# WiFi_Card_Led_Monitor.net
KiCad netlist of a schematic drawn in Altium Designer
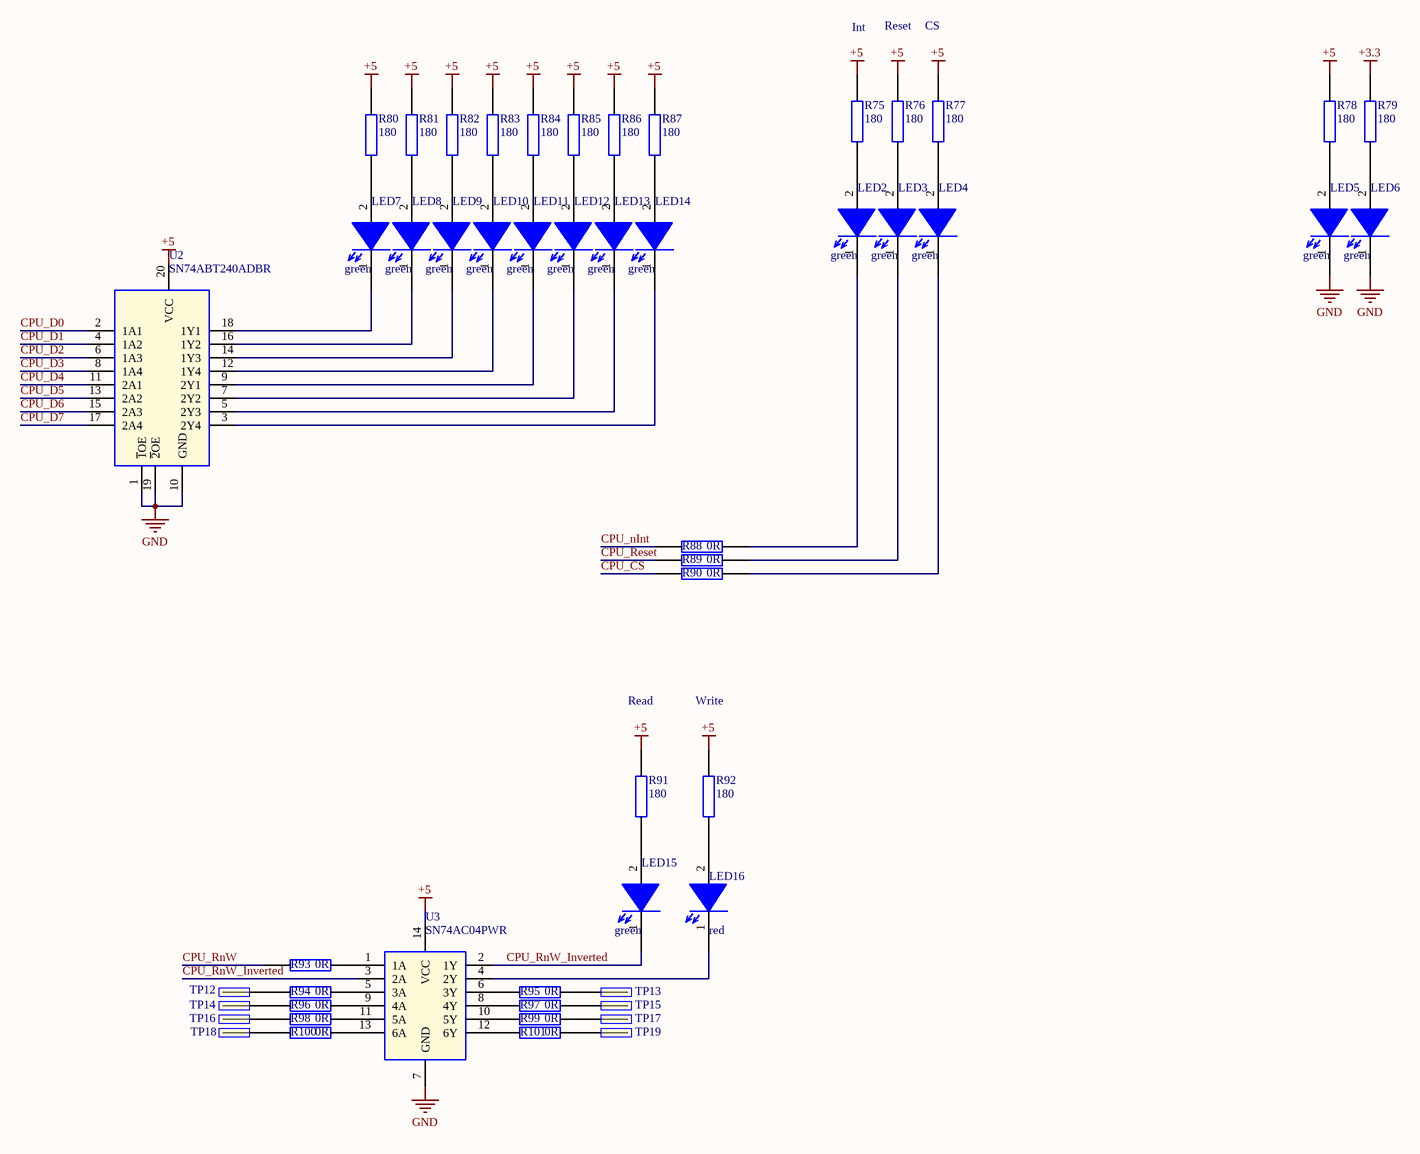
[diagram p0: WiFi_Card_Led_Monitor.SchDoc]

(export (version "E")
  (design (tool "Eeschema 10.0.6"))
  (components
    (comp (ref "LED2")
      (value "green")
      (footprint "0603_Diode")
      (description "Wurth Elektronik 0603 green")
      (fields
        (field (name "MANUFACTURER") "Wurth Electronics")
        (field (name "MANUFACTURER PART NUMBER") "150060GS75000")
      )
      (libsource (lib "Misc") (part "150060GS75000"))
    )
    (comp (ref "LED3")
      (value "green")
      (footprint "0603_Diode")
      (description "Wurth Elektronik 0603 green")
      (fields
        (field (name "MANUFACTURER") "Wurth Electronics")
        (field (name "MANUFACTURER PART NUMBER") "150060GS75000")
      )
      (libsource (lib "Misc") (part "150060GS75000"))
    )
    (comp (ref "LED4")
      (value "green")
      (footprint "0603_Diode")
      (description "Wurth Elektronik 0603 green")
      (fields
        (field (name "MANUFACTURER") "Wurth Electronics")
        (field (name "MANUFACTURER PART NUMBER") "150060GS75000")
      )
      (libsource (lib "Misc") (part "150060GS75000"))
    )
    (comp (ref "LED5")
      (value "green")
      (footprint "0603_Diode")
      (description "Wurth Elektronik 0603 green")
      (fields
        (field (name "MANUFACTURER") "Wurth Electronics")
        (field (name "MANUFACTURER PART NUMBER") "150060GS75000")
      )
      (libsource (lib "Misc") (part "150060GS75000"))
    )
    (comp (ref "LED6")
      (value "green")
      (footprint "0603_Diode")
      (description "Wurth Elektronik 0603 green")
      (fields
        (field (name "MANUFACTURER") "Wurth Electronics")
        (field (name "MANUFACTURER PART NUMBER") "150060GS75000")
      )
      (libsource (lib "Misc") (part "150060GS75000"))
    )
    (comp (ref "LED7")
      (value "green")
      (footprint "0603_Diode")
      (description "Wurth Elektronik 0603 green")
      (fields
        (field (name "MANUFACTURER") "Wurth Electronics")
        (field (name "MANUFACTURER PART NUMBER") "150060GS75000")
      )
      (libsource (lib "Misc") (part "150060GS75000"))
    )
    (comp (ref "LED8")
      (value "green")
      (footprint "0603_Diode")
      (description "Wurth Elektronik 0603 green")
      (fields
        (field (name "MANUFACTURER") "Wurth Electronics")
        (field (name "MANUFACTURER PART NUMBER") "150060GS75000")
      )
      (libsource (lib "Misc") (part "150060GS75000"))
    )
    (comp (ref "LED9")
      (value "green")
      (footprint "0603_Diode")
      (description "Wurth Elektronik 0603 green")
      (fields
        (field (name "MANUFACTURER") "Wurth Electronics")
        (field (name "MANUFACTURER PART NUMBER") "150060GS75000")
      )
      (libsource (lib "Misc") (part "150060GS75000"))
    )
    (comp (ref "LED10")
      (value "green")
      (footprint "0603_Diode")
      (description "Wurth Elektronik 0603 green")
      (fields
        (field (name "MANUFACTURER") "Wurth Electronics")
        (field (name "MANUFACTURER PART NUMBER") "150060GS75000")
      )
      (libsource (lib "Misc") (part "150060GS75000"))
    )
    (comp (ref "LED11")
      (value "green")
      (footprint "0603_Diode")
      (description "Wurth Elektronik 0603 green")
      (fields
        (field (name "MANUFACTURER") "Wurth Electronics")
        (field (name "MANUFACTURER PART NUMBER") "150060GS75000")
      )
      (libsource (lib "Misc") (part "150060GS75000"))
    )
    (comp (ref "LED12")
      (value "green")
      (footprint "0603_Diode")
      (description "Wurth Elektronik 0603 green")
      (fields
        (field (name "MANUFACTURER") "Wurth Electronics")
        (field (name "MANUFACTURER PART NUMBER") "150060GS75000")
      )
      (libsource (lib "Misc") (part "150060GS75000"))
    )
    (comp (ref "LED13")
      (value "green")
      (footprint "0603_Diode")
      (description "Wurth Elektronik 0603 green")
      (fields
        (field (name "MANUFACTURER") "Wurth Electronics")
        (field (name "MANUFACTURER PART NUMBER") "150060GS75000")
      )
      (libsource (lib "Misc") (part "150060GS75000"))
    )
    (comp (ref "LED14")
      (value "green")
      (footprint "0603_Diode")
      (description "Wurth Elektronik 0603 green")
      (fields
        (field (name "MANUFACTURER") "Wurth Electronics")
        (field (name "MANUFACTURER PART NUMBER") "150060GS75000")
      )
      (libsource (lib "Misc") (part "150060GS75000"))
    )
    (comp (ref "LED15")
      (value "green")
      (footprint "0603_Diode")
      (description "Wurth Elektronik 0603 green")
      (fields
        (field (name "MANUFACTURER") "Wurth Electronics")
        (field (name "MANUFACTURER PART NUMBER") "150060GS75000")
      )
      (libsource (lib "Misc") (part "150060GS75000"))
    )
    (comp (ref "LED16")
      (value "red")
      (footprint "0603_Diode")
      (description "Wurth Elektronik 0603 red")
      (fields
        (field (name "MANUFACTURER") "Wurth Electronics")
        (field (name "MANUFACTURER PART NUMBER") "150060GS75000")
      )
      (libsource (lib "Misc") (part "150060RS75000"))
    )
    (comp (ref "R75")
      (value "180")
      (footprint "0603")
      (description "YAGEO 0603 180 ohm")
      (fields
        (field (name "MOUSER PART NUMBER") "603-RC0603JR-070RL")
        (field (name "MANUFACTURER_PART_NUMBER") "RC0603JR-070RL")
      )
      (libsource (lib "Resistors") (part "RC0603FR-13180RL"))
    )
    (comp (ref "R76")
      (value "180")
      (footprint "0603")
      (description "YAGEO 0603 180 ohm")
      (fields
        (field (name "MOUSER PART NUMBER") "603-RC0603JR-070RL")
        (field (name "MANUFACTURER_PART_NUMBER") "RC0603JR-070RL")
      )
      (libsource (lib "Resistors") (part "RC0603FR-13180RL"))
    )
    (comp (ref "R77")
      (value "180")
      (footprint "0603")
      (description "YAGEO 0603 180 ohm")
      (fields
        (field (name "MOUSER PART NUMBER") "603-RC0603JR-070RL")
        (field (name "MANUFACTURER_PART_NUMBER") "RC0603JR-070RL")
      )
      (libsource (lib "Resistors") (part "RC0603FR-13180RL"))
    )
    (comp (ref "R78")
      (value "180")
      (footprint "0603")
      (description "YAGEO 0603 180 ohm")
      (fields
        (field (name "MOUSER PART NUMBER") "603-RC0603JR-070RL")
        (field (name "MANUFACTURER_PART_NUMBER") "RC0603JR-070RL")
      )
      (libsource (lib "Resistors") (part "RC0603FR-13180RL"))
    )
    (comp (ref "R79")
      (value "180")
      (footprint "0603")
      (description "YAGEO 0603 180 ohm")
      (fields
        (field (name "MOUSER PART NUMBER") "603-RC0603JR-070RL")
        (field (name "MANUFACTURER_PART_NUMBER") "RC0603JR-070RL")
      )
      (libsource (lib "Resistors") (part "RC0603FR-13180RL"))
    )
    (comp (ref "R80")
      (value "180")
      (footprint "0603")
      (description "YAGEO 0603 180 ohm")
      (fields
        (field (name "MOUSER PART NUMBER") "603-RC0603JR-070RL")
        (field (name "MANUFACTURER_PART_NUMBER") "RC0603JR-070RL")
      )
      (libsource (lib "Resistors") (part "RC0603FR-13180RL"))
    )
    (comp (ref "R81")
      (value "180")
      (footprint "0603")
      (description "YAGEO 0603 180 ohm")
      (fields
        (field (name "MOUSER PART NUMBER") "603-RC0603JR-070RL")
        (field (name "MANUFACTURER_PART_NUMBER") "RC0603JR-070RL")
      )
      (libsource (lib "Resistors") (part "RC0603FR-13180RL"))
    )
    (comp (ref "R82")
      (value "180")
      (footprint "0603")
      (description "YAGEO 0603 180 ohm")
      (fields
        (field (name "MOUSER PART NUMBER") "603-RC0603JR-070RL")
        (field (name "MANUFACTURER_PART_NUMBER") "RC0603JR-070RL")
      )
      (libsource (lib "Resistors") (part "RC0603FR-13180RL"))
    )
    (comp (ref "R83")
      (value "180")
      (footprint "0603")
      (description "YAGEO 0603 180 ohm")
      (fields
        (field (name "MOUSER PART NUMBER") "603-RC0603JR-070RL")
        (field (name "MANUFACTURER_PART_NUMBER") "RC0603JR-070RL")
      )
      (libsource (lib "Resistors") (part "RC0603FR-13180RL"))
    )
    (comp (ref "R84")
      (value "180")
      (footprint "0603")
      (description "YAGEO 0603 180 ohm")
      (fields
        (field (name "MOUSER PART NUMBER") "603-RC0603JR-070RL")
        (field (name "MANUFACTURER_PART_NUMBER") "RC0603JR-070RL")
      )
      (libsource (lib "Resistors") (part "RC0603FR-13180RL"))
    )
    (comp (ref "R85")
      (value "180")
      (footprint "0603")
      (description "YAGEO 0603 180 ohm")
      (fields
        (field (name "MOUSER PART NUMBER") "603-RC0603JR-070RL")
        (field (name "MANUFACTURER_PART_NUMBER") "RC0603JR-070RL")
      )
      (libsource (lib "Resistors") (part "RC0603FR-13180RL"))
    )
    (comp (ref "R86")
      (value "180")
      (footprint "0603")
      (description "YAGEO 0603 180 ohm")
      (fields
        (field (name "MOUSER PART NUMBER") "603-RC0603JR-070RL")
        (field (name "MANUFACTURER_PART_NUMBER") "RC0603JR-070RL")
      )
      (libsource (lib "Resistors") (part "RC0603FR-13180RL"))
    )
    (comp (ref "R87")
      (value "180")
      (footprint "0603")
      (description "YAGEO 0603 180 ohm")
      (fields
        (field (name "MOUSER PART NUMBER") "603-RC0603JR-070RL")
        (field (name "MANUFACTURER_PART_NUMBER") "RC0603JR-070RL")
      )
      (libsource (lib "Resistors") (part "RC0603FR-13180RL"))
    )
    (comp (ref "R88")
      (value "0R")
      (footprint "0603")
      (description "YAGEO 0603 0 ohm")
      (fields
        (field (name "MOUSER PART NUMBER") "603-RC0603JR-070RL")
        (field (name "MANUFACTURER_PART_NUMBER") "RC0603JR-070RL")
      )
      (libsource (lib "Resistors") (part "RC0603JR-070RL"))
    )
    (comp (ref "R89")
      (value "0R")
      (footprint "0603")
      (description "YAGEO 0603 0 ohm")
      (fields
        (field (name "MOUSER PART NUMBER") "603-RC0603JR-070RL")
        (field (name "MANUFACTURER_PART_NUMBER") "RC0603JR-070RL")
      )
      (libsource (lib "Resistors") (part "RC0603JR-070RL"))
    )
    (comp (ref "R90")
      (value "0R")
      (footprint "0603")
      (description "YAGEO 0603 0 ohm")
      (fields
        (field (name "MOUSER PART NUMBER") "603-RC0603JR-070RL")
        (field (name "MANUFACTURER_PART_NUMBER") "RC0603JR-070RL")
      )
      (libsource (lib "Resistors") (part "RC0603JR-070RL"))
    )
    (comp (ref "R91")
      (value "180")
      (footprint "0603")
      (description "YAGEO 0603 180 ohm")
      (fields
        (field (name "MOUSER PART NUMBER") "603-RC0603JR-070RL")
        (field (name "MANUFACTURER_PART_NUMBER") "RC0603JR-070RL")
      )
      (libsource (lib "Resistors") (part "RC0603FR-13180RL"))
    )
    (comp (ref "R92")
      (value "180")
      (footprint "0603")
      (description "YAGEO 0603 180 ohm")
      (fields
        (field (name "MOUSER PART NUMBER") "603-RC0603JR-070RL")
        (field (name "MANUFACTURER_PART_NUMBER") "RC0603JR-070RL")
      )
      (libsource (lib "Resistors") (part "RC0603FR-13180RL"))
    )
    (comp (ref "R93")
      (value "0R")
      (footprint "0603")
      (description "YAGEO 0603 0 ohm")
      (fields
        (field (name "MOUSER PART NUMBER") "603-RC0603JR-070RL")
        (field (name "MANUFACTURER_PART_NUMBER") "RC0603JR-070RL")
      )
      (libsource (lib "Resistors") (part "RC0603JR-070RL"))
    )
    (comp (ref "R94")
      (value "0R")
      (footprint "0603")
      (description "YAGEO 0603 0 ohm")
      (fields
        (field (name "MOUSER PART NUMBER") "603-RC0603JR-070RL")
        (field (name "MANUFACTURER_PART_NUMBER") "RC0603JR-070RL")
      )
      (libsource (lib "Resistors") (part "RC0603JR-070RL"))
    )
    (comp (ref "R95")
      (value "0R")
      (footprint "0603")
      (description "YAGEO 0603 0 ohm")
      (fields
        (field (name "MOUSER PART NUMBER") "603-RC0603JR-070RL")
        (field (name "MANUFACTURER_PART_NUMBER") "RC0603JR-070RL")
      )
      (libsource (lib "Resistors") (part "RC0603JR-070RL"))
    )
    (comp (ref "R96")
      (value "0R")
      (footprint "0603")
      (description "YAGEO 0603 0 ohm")
      (fields
        (field (name "MOUSER PART NUMBER") "603-RC0603JR-070RL")
        (field (name "MANUFACTURER_PART_NUMBER") "RC0603JR-070RL")
      )
      (libsource (lib "Resistors") (part "RC0603JR-070RL"))
    )
    (comp (ref "R97")
      (value "0R")
      (footprint "0603")
      (description "YAGEO 0603 0 ohm")
      (fields
        (field (name "MOUSER PART NUMBER") "603-RC0603JR-070RL")
        (field (name "MANUFACTURER_PART_NUMBER") "RC0603JR-070RL")
      )
      (libsource (lib "Resistors") (part "RC0603JR-070RL"))
    )
    (comp (ref "R98")
      (value "0R")
      (footprint "0603")
      (description "YAGEO 0603 0 ohm")
      (fields
        (field (name "MOUSER PART NUMBER") "603-RC0603JR-070RL")
        (field (name "MANUFACTURER_PART_NUMBER") "RC0603JR-070RL")
      )
      (libsource (lib "Resistors") (part "RC0603JR-070RL"))
    )
    (comp (ref "R99")
      (value "0R")
      (footprint "0603")
      (description "YAGEO 0603 0 ohm")
      (fields
        (field (name "MOUSER PART NUMBER") "603-RC0603JR-070RL")
        (field (name "MANUFACTURER_PART_NUMBER") "RC0603JR-070RL")
      )
      (libsource (lib "Resistors") (part "RC0603JR-070RL"))
    )
    (comp (ref "R100")
      (value "0R")
      (footprint "0603")
      (description "YAGEO 0603 0 ohm")
      (fields
        (field (name "MOUSER PART NUMBER") "603-RC0603JR-070RL")
        (field (name "MANUFACTURER_PART_NUMBER") "RC0603JR-070RL")
      )
      (libsource (lib "Resistors") (part "RC0603JR-070RL"))
    )
    (comp (ref "R101")
      (value "0R")
      (footprint "0603")
      (description "YAGEO 0603 0 ohm")
      (fields
        (field (name "MOUSER PART NUMBER") "603-RC0603JR-070RL")
        (field (name "MANUFACTURER_PART_NUMBER") "RC0603JR-070RL")
      )
      (libsource (lib "Resistors") (part "RC0603JR-070RL"))
    )
    (comp (ref "TP12")
      (value "TP")
      (footprint "TP")
      (fields
        (field (name "MANUFACTURER") "Samtec")
        (field (name "MANUFACTURER PART NUMBER") "TST-105-01-G-D")
      )
      (libsource (lib "Misc") (part "TP"))
    )
    (comp (ref "TP13")
      (value "TP")
      (footprint "TP")
      (fields
        (field (name "MANUFACTURER") "Samtec")
        (field (name "MANUFACTURER PART NUMBER") "TST-105-01-G-D")
      )
      (libsource (lib "") (part "TP_1"))
    )
    (comp (ref "TP14")
      (value "TP")
      (footprint "TP")
      (fields
        (field (name "MANUFACTURER") "Samtec")
        (field (name "MANUFACTURER PART NUMBER") "TST-105-01-G-D")
      )
      (libsource (lib "Misc") (part "TP"))
    )
    (comp (ref "TP15")
      (value "TP")
      (footprint "TP")
      (fields
        (field (name "MANUFACTURER") "Samtec")
        (field (name "MANUFACTURER PART NUMBER") "TST-105-01-G-D")
      )
      (libsource (lib "") (part "TP_1"))
    )
    (comp (ref "TP16")
      (value "TP")
      (footprint "TP")
      (fields
        (field (name "MANUFACTURER") "Samtec")
        (field (name "MANUFACTURER PART NUMBER") "TST-105-01-G-D")
      )
      (libsource (lib "Misc") (part "TP"))
    )
    (comp (ref "TP17")
      (value "TP")
      (footprint "TP")
      (fields
        (field (name "MANUFACTURER") "Samtec")
        (field (name "MANUFACTURER PART NUMBER") "TST-105-01-G-D")
      )
      (libsource (lib "") (part "TP_1"))
    )
    (comp (ref "TP18")
      (value "TP")
      (footprint "TP")
      (fields
        (field (name "MANUFACTURER") "Samtec")
        (field (name "MANUFACTURER PART NUMBER") "TST-105-01-G-D")
      )
      (libsource (lib "Misc") (part "TP"))
    )
    (comp (ref "TP19")
      (value "TP")
      (footprint "TP")
      (fields
        (field (name "MANUFACTURER") "Samtec")
        (field (name "MANUFACTURER PART NUMBER") "TST-105-01-G-D")
      )
      (libsource (lib "") (part "TP_1"))
    )
    (comp (ref "U2")
      (value "SN74ABT240ADBR")
      (footprint "SOP65P780X200-20N")
      (description "Octal Buffers/Drivers With 3-State Outputs")
      (fields (field (name "MOUSER PART NUMBER") "595-SN74ABT240ADBR"))
      (libsource (lib "Logic") (part "SN74ABT240ADBR"))
    )
    (comp (ref "U3")
      (value "SN74AC04PWR")
      (footprint "SOP65P640X120-14N")
      (description "Hex Inverters")
      (fields (field (name "MOUSER PART NUMBER") "595-SN74AC04PWR"))
      (libsource (lib "Logic") (part "SN74AC04PWR"))
    )
  )
  (nets
    (net (code "1") (name "+3.3") (class "Default")
      (node (ref "R79") (pin "2") (pinfunction "2_2") (pintype "passive"))
    )
    (net (code "2") (name "+5") (class "Default")
      (node (ref "R75") (pin "2") (pinfunction "2_2") (pintype "passive"))
      (node (ref "R76") (pin "2") (pinfunction "2_2") (pintype "passive"))
      (node (ref "R77") (pin "2") (pinfunction "2_2") (pintype "passive"))
      (node (ref "R78") (pin "2") (pinfunction "2_2") (pintype "passive"))
      (node (ref "R80") (pin "2") (pinfunction "2_2") (pintype "passive"))
      (node (ref "R81") (pin "2") (pinfunction "2_2") (pintype "passive"))
      (node (ref "R82") (pin "2") (pinfunction "2_2") (pintype "passive"))
      (node (ref "R83") (pin "2") (pinfunction "2_2") (pintype "passive"))
      (node (ref "R84") (pin "2") (pinfunction "2_2") (pintype "passive"))
      (node (ref "R85") (pin "2") (pinfunction "2_2") (pintype "passive"))
      (node (ref "R86") (pin "2") (pinfunction "2_2") (pintype "passive"))
      (node (ref "R87") (pin "2") (pinfunction "2_2") (pintype "passive"))
      (node (ref "R91") (pin "2") (pinfunction "2_2") (pintype "passive"))
      (node (ref "R92") (pin "2") (pinfunction "2_2") (pintype "passive"))
      (node (ref "U2") (pin "20") (pinfunction "VCC_20") (pintype "passive"))
      (node (ref "U3") (pin "14") (pinfunction "VCC_14") (pintype "passive"))
    )
    (net (code "3") (name "/CPU_CS") (class "Default")
      (node (ref "R90") (pin "1") (pinfunction "1_1") (pintype "passive"))
    )
    (net (code "4") (name "/CPU_D0") (class "Default")
      (node (ref "U2") (pin "2") (pinfunction "1A1_2") (pintype "passive"))
    )
    (net (code "5") (name "/CPU_D1") (class "Default")
      (node (ref "U2") (pin "4") (pinfunction "1A2_4") (pintype "passive"))
    )
    (net (code "6") (name "/CPU_D2") (class "Default")
      (node (ref "U2") (pin "6") (pinfunction "1A3_6") (pintype "passive"))
    )
    (net (code "7") (name "/CPU_D3") (class "Default")
      (node (ref "U2") (pin "8") (pinfunction "1A4_8") (pintype "passive"))
    )
    (net (code "8") (name "/CPU_D4") (class "Default")
      (node (ref "U2") (pin "11") (pinfunction "2A1_11") (pintype "passive"))
    )
    (net (code "9") (name "/CPU_D5") (class "Default")
      (node (ref "U2") (pin "13") (pinfunction "2A2_13") (pintype "passive"))
    )
    (net (code "10") (name "/CPU_D6") (class "Default")
      (node (ref "U2") (pin "15") (pinfunction "2A3_15") (pintype "passive"))
    )
    (net (code "11") (name "/CPU_D7") (class "Default")
      (node (ref "U2") (pin "17") (pinfunction "2A4_17") (pintype "passive"))
    )
    (net (code "12") (name "/CPU_Reset") (class "Default")
      (node (ref "R89") (pin "1") (pinfunction "1_1") (pintype "passive"))
    )
    (net (code "13") (name "/CPU_RnW") (class "Default")
      (node (ref "R93") (pin "1") (pinfunction "1_1") (pintype "passive"))
    )
    (net (code "14") (name "/CPU_RnW_Inverted") (class "Default")
      (node (ref "LED15") (pin "1") (pinfunction "K_1") (pintype "passive"))
      (node (ref "U3") (pin "2") (pinfunction "1Y_2") (pintype "passive"))
      (node (ref "U3") (pin "3") (pinfunction "2A_3") (pintype "passive"))
    )
    (net (code "15") (name "/CPU_nInt") (class "Default")
      (node (ref "R88") (pin "1") (pinfunction "1_1") (pintype "passive"))
    )
    (net (code "16") (name "GND") (class "Default")
      (node (ref "LED5") (pin "1") (pinfunction "K_1") (pintype "passive"))
      (node (ref "LED6") (pin "1") (pinfunction "K_1") (pintype "passive"))
      (node (ref "U2") (pin "1") (pinfunction "~{1}OE_1") (pintype "passive"))
      (node (ref "U2") (pin "10") (pinfunction "GND_10") (pintype "passive"))
      (node (ref "U2") (pin "19") (pinfunction "~{2}OE_19") (pintype "passive"))
      (node (ref "U3") (pin "7") (pinfunction "GND_7") (pintype "passive"))
    )
    (net (code "17") (name "Net-(LED2-A)") (class "Default")
      (node (ref "LED2") (pin "2") (pinfunction "A_2") (pintype "passive"))
      (node (ref "R75") (pin "1") (pinfunction "1_1") (pintype "passive"))
    )
    (net (code "18") (name "Net-(LED2-K)") (class "Default")
      (node (ref "LED2") (pin "1") (pinfunction "K_1") (pintype "passive"))
      (node (ref "R88") (pin "2") (pinfunction "2_2") (pintype "passive"))
    )
    (net (code "19") (name "Net-(LED3-A)") (class "Default")
      (node (ref "LED3") (pin "2") (pinfunction "A_2") (pintype "passive"))
      (node (ref "R76") (pin "1") (pinfunction "1_1") (pintype "passive"))
    )
    (net (code "20") (name "Net-(LED3-K)") (class "Default")
      (node (ref "LED3") (pin "1") (pinfunction "K_1") (pintype "passive"))
      (node (ref "R89") (pin "2") (pinfunction "2_2") (pintype "passive"))
    )
    (net (code "21") (name "Net-(LED4-A)") (class "Default")
      (node (ref "LED4") (pin "2") (pinfunction "A_2") (pintype "passive"))
      (node (ref "R77") (pin "1") (pinfunction "1_1") (pintype "passive"))
    )
    (net (code "22") (name "Net-(LED4-K)") (class "Default")
      (node (ref "LED4") (pin "1") (pinfunction "K_1") (pintype "passive"))
      (node (ref "R90") (pin "2") (pinfunction "2_2") (pintype "passive"))
    )
    (net (code "23") (name "Net-(LED5-A)") (class "Default")
      (node (ref "LED5") (pin "2") (pinfunction "A_2") (pintype "passive"))
      (node (ref "R78") (pin "1") (pinfunction "1_1") (pintype "passive"))
    )
    (net (code "24") (name "Net-(LED6-A)") (class "Default")
      (node (ref "LED6") (pin "2") (pinfunction "A_2") (pintype "passive"))
      (node (ref "R79") (pin "1") (pinfunction "1_1") (pintype "passive"))
    )
    (net (code "25") (name "Net-(LED7-A)") (class "Default")
      (node (ref "LED7") (pin "2") (pinfunction "A_2") (pintype "passive"))
      (node (ref "R80") (pin "1") (pinfunction "1_1") (pintype "passive"))
    )
    (net (code "26") (name "Net-(LED7-K)") (class "Default")
      (node (ref "LED7") (pin "1") (pinfunction "K_1") (pintype "passive"))
      (node (ref "U2") (pin "18") (pinfunction "1Y1_18") (pintype "passive"))
    )
    (net (code "27") (name "Net-(LED8-A)") (class "Default")
      (node (ref "LED8") (pin "2") (pinfunction "A_2") (pintype "passive"))
      (node (ref "R81") (pin "1") (pinfunction "1_1") (pintype "passive"))
    )
    (net (code "28") (name "Net-(LED8-K)") (class "Default")
      (node (ref "LED8") (pin "1") (pinfunction "K_1") (pintype "passive"))
      (node (ref "U2") (pin "16") (pinfunction "1Y2_16") (pintype "passive"))
    )
    (net (code "29") (name "Net-(LED9-A)") (class "Default")
      (node (ref "LED9") (pin "2") (pinfunction "A_2") (pintype "passive"))
      (node (ref "R82") (pin "1") (pinfunction "1_1") (pintype "passive"))
    )
    (net (code "30") (name "Net-(LED9-K)") (class "Default")
      (node (ref "LED9") (pin "1") (pinfunction "K_1") (pintype "passive"))
      (node (ref "U2") (pin "14") (pinfunction "1Y3_14") (pintype "passive"))
    )
    (net (code "31") (name "Net-(LED10-A)") (class "Default")
      (node (ref "LED10") (pin "2") (pinfunction "A_2") (pintype "passive"))
      (node (ref "R83") (pin "1") (pinfunction "1_1") (pintype "passive"))
    )
    (net (code "32") (name "Net-(LED10-K)") (class "Default")
      (node (ref "LED10") (pin "1") (pinfunction "K_1") (pintype "passive"))
      (node (ref "U2") (pin "12") (pinfunction "1Y4_12") (pintype "passive"))
    )
    (net (code "33") (name "Net-(LED11-A)") (class "Default")
      (node (ref "LED11") (pin "2") (pinfunction "A_2") (pintype "passive"))
      (node (ref "R84") (pin "1") (pinfunction "1_1") (pintype "passive"))
    )
    (net (code "34") (name "Net-(LED11-K)") (class "Default")
      (node (ref "LED11") (pin "1") (pinfunction "K_1") (pintype "passive"))
      (node (ref "U2") (pin "9") (pinfunction "2Y1_9") (pintype "passive"))
    )
    (net (code "35") (name "Net-(LED12-A)") (class "Default")
      (node (ref "LED12") (pin "2") (pinfunction "A_2") (pintype "passive"))
      (node (ref "R85") (pin "1") (pinfunction "1_1") (pintype "passive"))
    )
    (net (code "36") (name "Net-(LED12-K)") (class "Default")
      (node (ref "LED12") (pin "1") (pinfunction "K_1") (pintype "passive"))
      (node (ref "U2") (pin "7") (pinfunction "2Y2_7") (pintype "passive"))
    )
    (net (code "37") (name "Net-(LED13-A)") (class "Default")
      (node (ref "LED13") (pin "2") (pinfunction "A_2") (pintype "passive"))
      (node (ref "R86") (pin "1") (pinfunction "1_1") (pintype "passive"))
    )
    (net (code "38") (name "Net-(LED13-K)") (class "Default")
      (node (ref "LED13") (pin "1") (pinfunction "K_1") (pintype "passive"))
      (node (ref "U2") (pin "5") (pinfunction "2Y3_5") (pintype "passive"))
    )
    (net (code "39") (name "Net-(LED14-A)") (class "Default")
      (node (ref "LED14") (pin "2") (pinfunction "A_2") (pintype "passive"))
      (node (ref "R87") (pin "1") (pinfunction "1_1") (pintype "passive"))
    )
    (net (code "40") (name "Net-(LED14-K)") (class "Default")
      (node (ref "LED14") (pin "1") (pinfunction "K_1") (pintype "passive"))
      (node (ref "U2") (pin "3") (pinfunction "2Y4_3") (pintype "passive"))
    )
    (net (code "41") (name "Net-(LED15-A)") (class "Default")
      (node (ref "LED15") (pin "2") (pinfunction "A_2") (pintype "passive"))
      (node (ref "R91") (pin "1") (pinfunction "1_1") (pintype "passive"))
    )
    (net (code "42") (name "Net-(LED16-A)") (class "Default")
      (node (ref "LED16") (pin "2") (pinfunction "A_2") (pintype "passive"))
      (node (ref "R92") (pin "1") (pinfunction "1_1") (pintype "passive"))
    )
    (net (code "43") (name "Net-(LED16-K)") (class "Default")
      (node (ref "LED16") (pin "1") (pinfunction "K_1") (pintype "passive"))
      (node (ref "U3") (pin "4") (pinfunction "2Y_4") (pintype "passive"))
    )
    (net (code "44") (name "Net-(R94-Pad1)") (class "Default")
      (node (ref "R94") (pin "1") (pinfunction "1_1") (pintype "passive"))
      (node (ref "TP12") (pin "1") (pinfunction "1_1") (pintype "passive"))
    )
    (net (code "45") (name "Net-(R95-Pad2)") (class "Default")
      (node (ref "R95") (pin "2") (pinfunction "2_2") (pintype "passive"))
      (node (ref "TP13") (pin "1") (pinfunction "1_1") (pintype "passive"))
    )
    (net (code "46") (name "Net-(R96-Pad1)") (class "Default")
      (node (ref "R96") (pin "1") (pinfunction "1_1") (pintype "passive"))
      (node (ref "TP14") (pin "1") (pinfunction "1_1") (pintype "passive"))
    )
    (net (code "47") (name "Net-(R97-Pad2)") (class "Default")
      (node (ref "R97") (pin "2") (pinfunction "2_2") (pintype "passive"))
      (node (ref "TP15") (pin "1") (pinfunction "1_1") (pintype "passive"))
    )
    (net (code "48") (name "Net-(R98-Pad1)") (class "Default")
      (node (ref "R98") (pin "1") (pinfunction "1_1") (pintype "passive"))
      (node (ref "TP16") (pin "1") (pinfunction "1_1") (pintype "passive"))
    )
    (net (code "49") (name "Net-(R99-Pad2)") (class "Default")
      (node (ref "R99") (pin "2") (pinfunction "2_2") (pintype "passive"))
      (node (ref "TP17") (pin "1") (pinfunction "1_1") (pintype "passive"))
    )
    (net (code "50") (name "Net-(R100-Pad1)") (class "Default")
      (node (ref "R100") (pin "1") (pinfunction "1_1") (pintype "passive"))
      (node (ref "TP18") (pin "1") (pinfunction "1_1") (pintype "passive"))
    )
    (net (code "51") (name "Net-(R101-Pad2)") (class "Default")
      (node (ref "R101") (pin "2") (pinfunction "2_2") (pintype "passive"))
      (node (ref "TP19") (pin "1") (pinfunction "1_1") (pintype "passive"))
    )
    (net (code "52") (name "Net-(U3-1A)") (class "Default")
      (node (ref "R93") (pin "2") (pinfunction "2_2") (pintype "passive"))
      (node (ref "U3") (pin "1") (pinfunction "1A_1") (pintype "passive"))
    )
    (net (code "53") (name "Net-(U3-3A)") (class "Default")
      (node (ref "R94") (pin "2") (pinfunction "2_2") (pintype "passive"))
      (node (ref "U3") (pin "5") (pinfunction "3A_5") (pintype "passive"))
    )
    (net (code "54") (name "Net-(U3-3Y)") (class "Default")
      (node (ref "R95") (pin "1") (pinfunction "1_1") (pintype "passive"))
      (node (ref "U3") (pin "6") (pinfunction "3Y_6") (pintype "passive"))
    )
    (net (code "55") (name "Net-(U3-4A)") (class "Default")
      (node (ref "R96") (pin "2") (pinfunction "2_2") (pintype "passive"))
      (node (ref "U3") (pin "9") (pinfunction "4A_9") (pintype "passive"))
    )
    (net (code "56") (name "Net-(U3-4Y)") (class "Default")
      (node (ref "R97") (pin "1") (pinfunction "1_1") (pintype "passive"))
      (node (ref "U3") (pin "8") (pinfunction "4Y_8") (pintype "passive"))
    )
    (net (code "57") (name "Net-(U3-5A)") (class "Default")
      (node (ref "R98") (pin "2") (pinfunction "2_2") (pintype "passive"))
      (node (ref "U3") (pin "11") (pinfunction "5A_11") (pintype "passive"))
    )
    (net (code "58") (name "Net-(U3-5Y)") (class "Default")
      (node (ref "R99") (pin "1") (pinfunction "1_1") (pintype "passive"))
      (node (ref "U3") (pin "10") (pinfunction "5Y_10") (pintype "passive"))
    )
    (net (code "59") (name "Net-(U3-6A)") (class "Default")
      (node (ref "R100") (pin "2") (pinfunction "2_2") (pintype "passive"))
      (node (ref "U3") (pin "13") (pinfunction "6A_13") (pintype "passive"))
    )
    (net (code "60") (name "Net-(U3-6Y)") (class "Default")
      (node (ref "R101") (pin "1") (pinfunction "1_1") (pintype "passive"))
      (node (ref "U3") (pin "12") (pinfunction "6Y_12") (pintype "passive"))
    )
  )
)
